# bg_MCU.net
KiCad netlist of a schematic drawn in Altium Designer
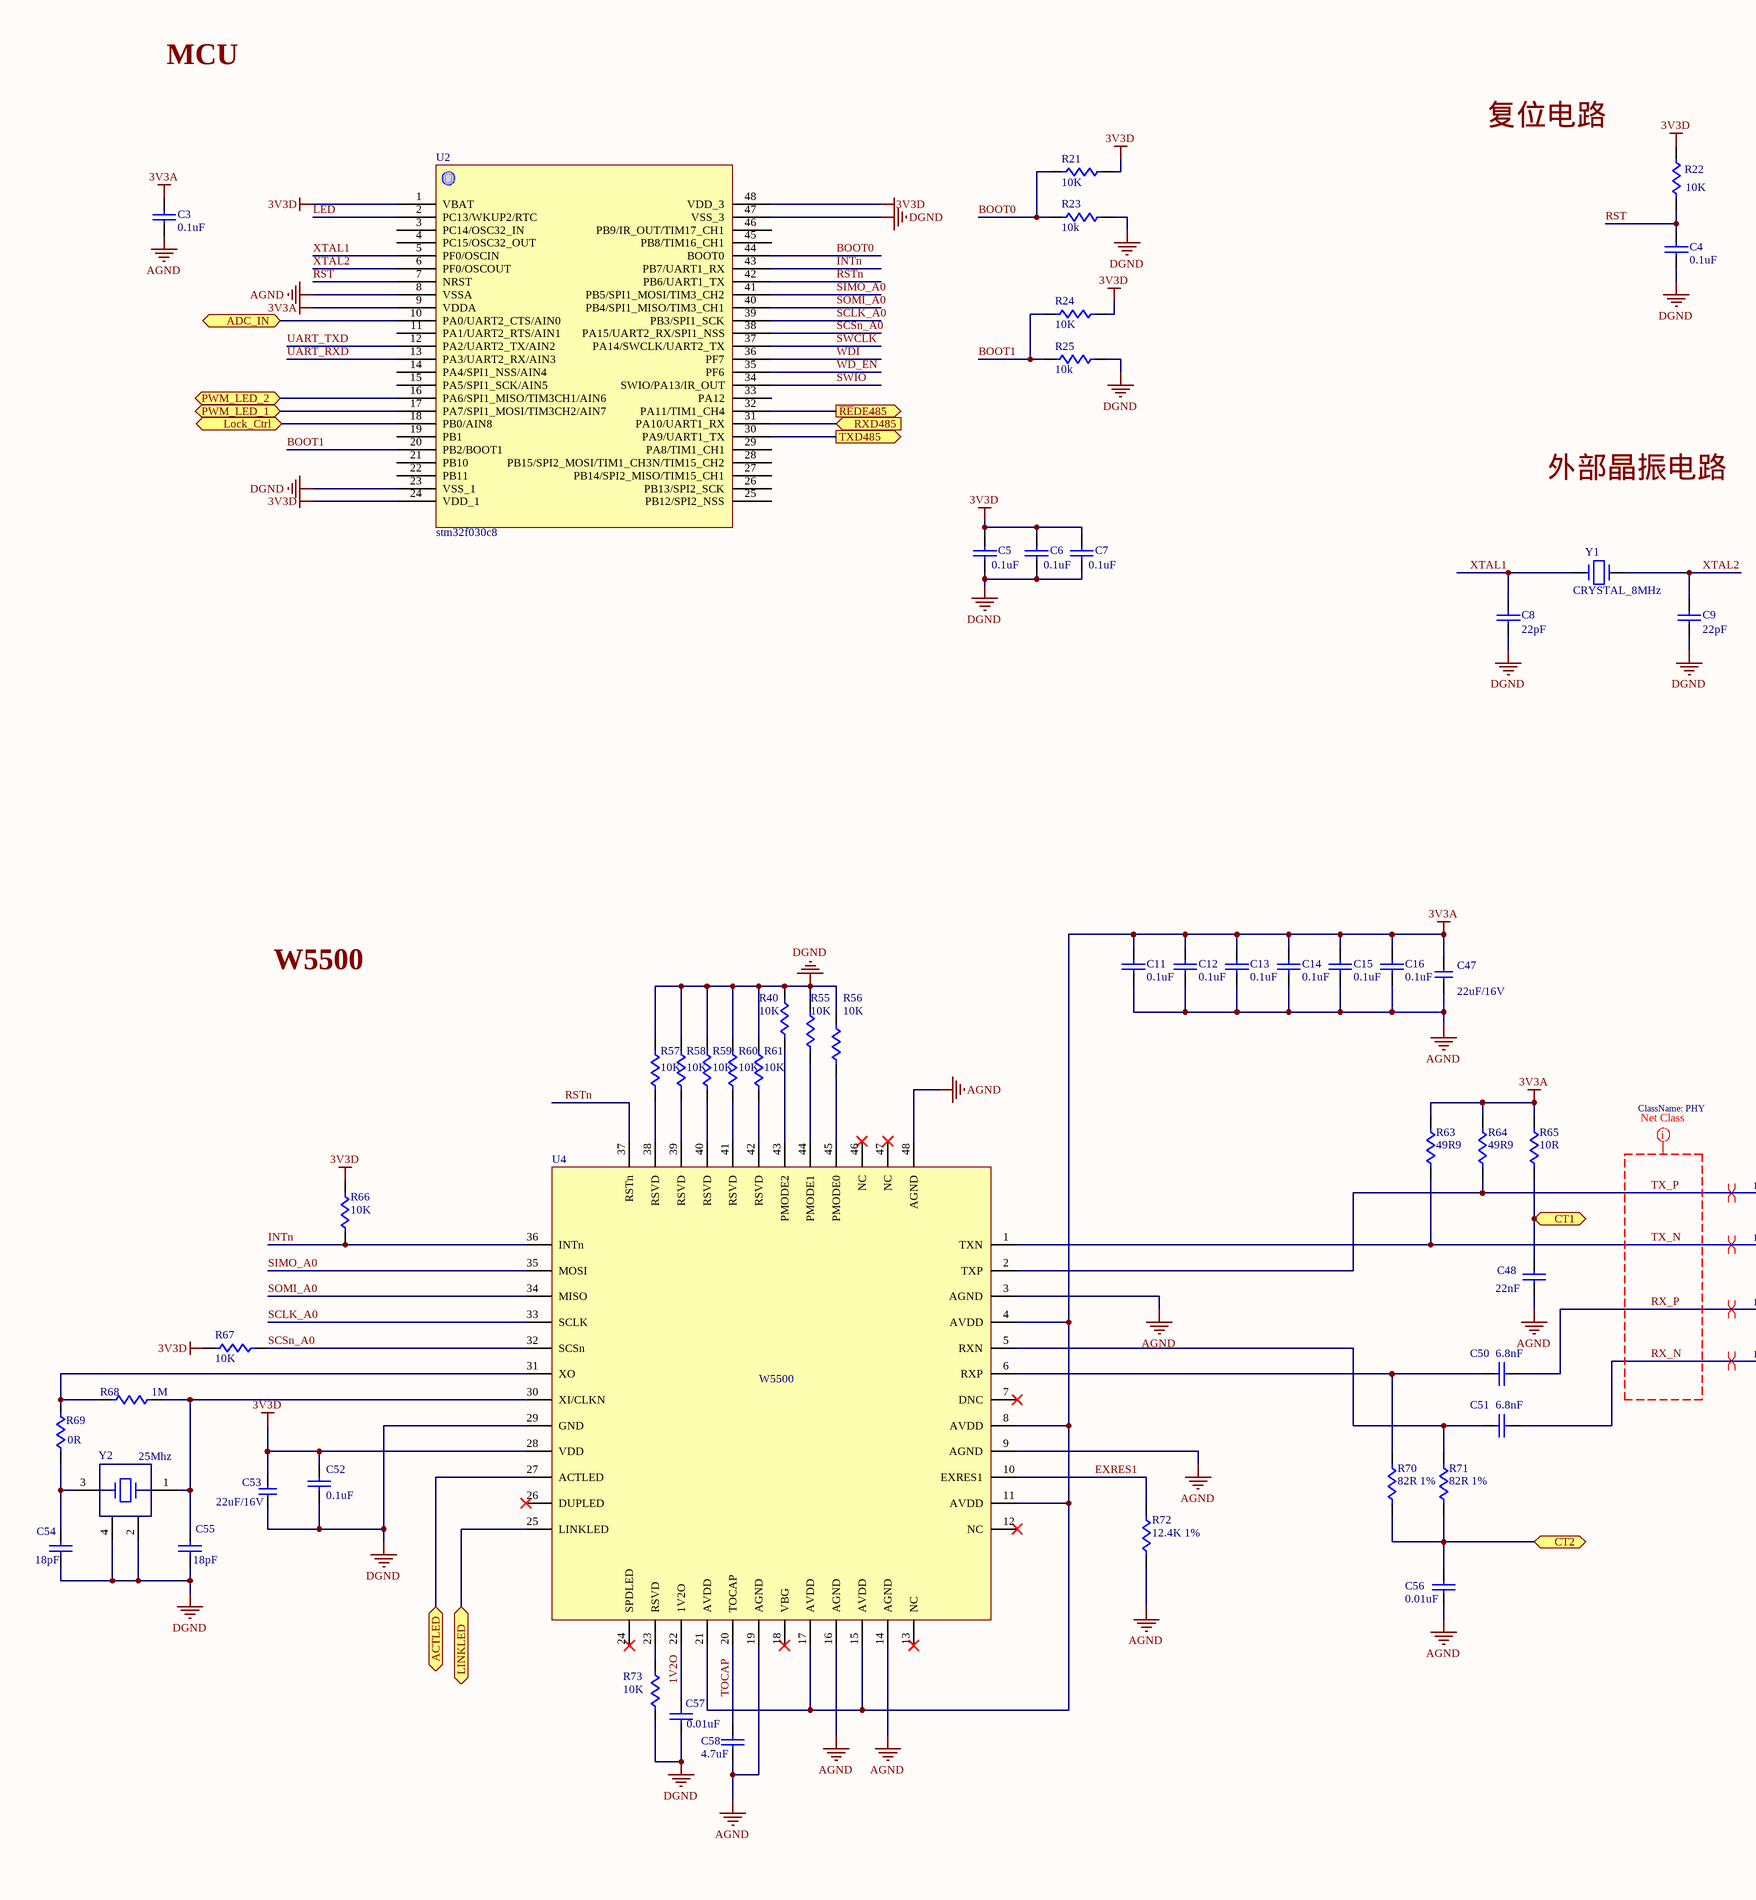
[diagram p0: bg_MCU.SchDoc, left]
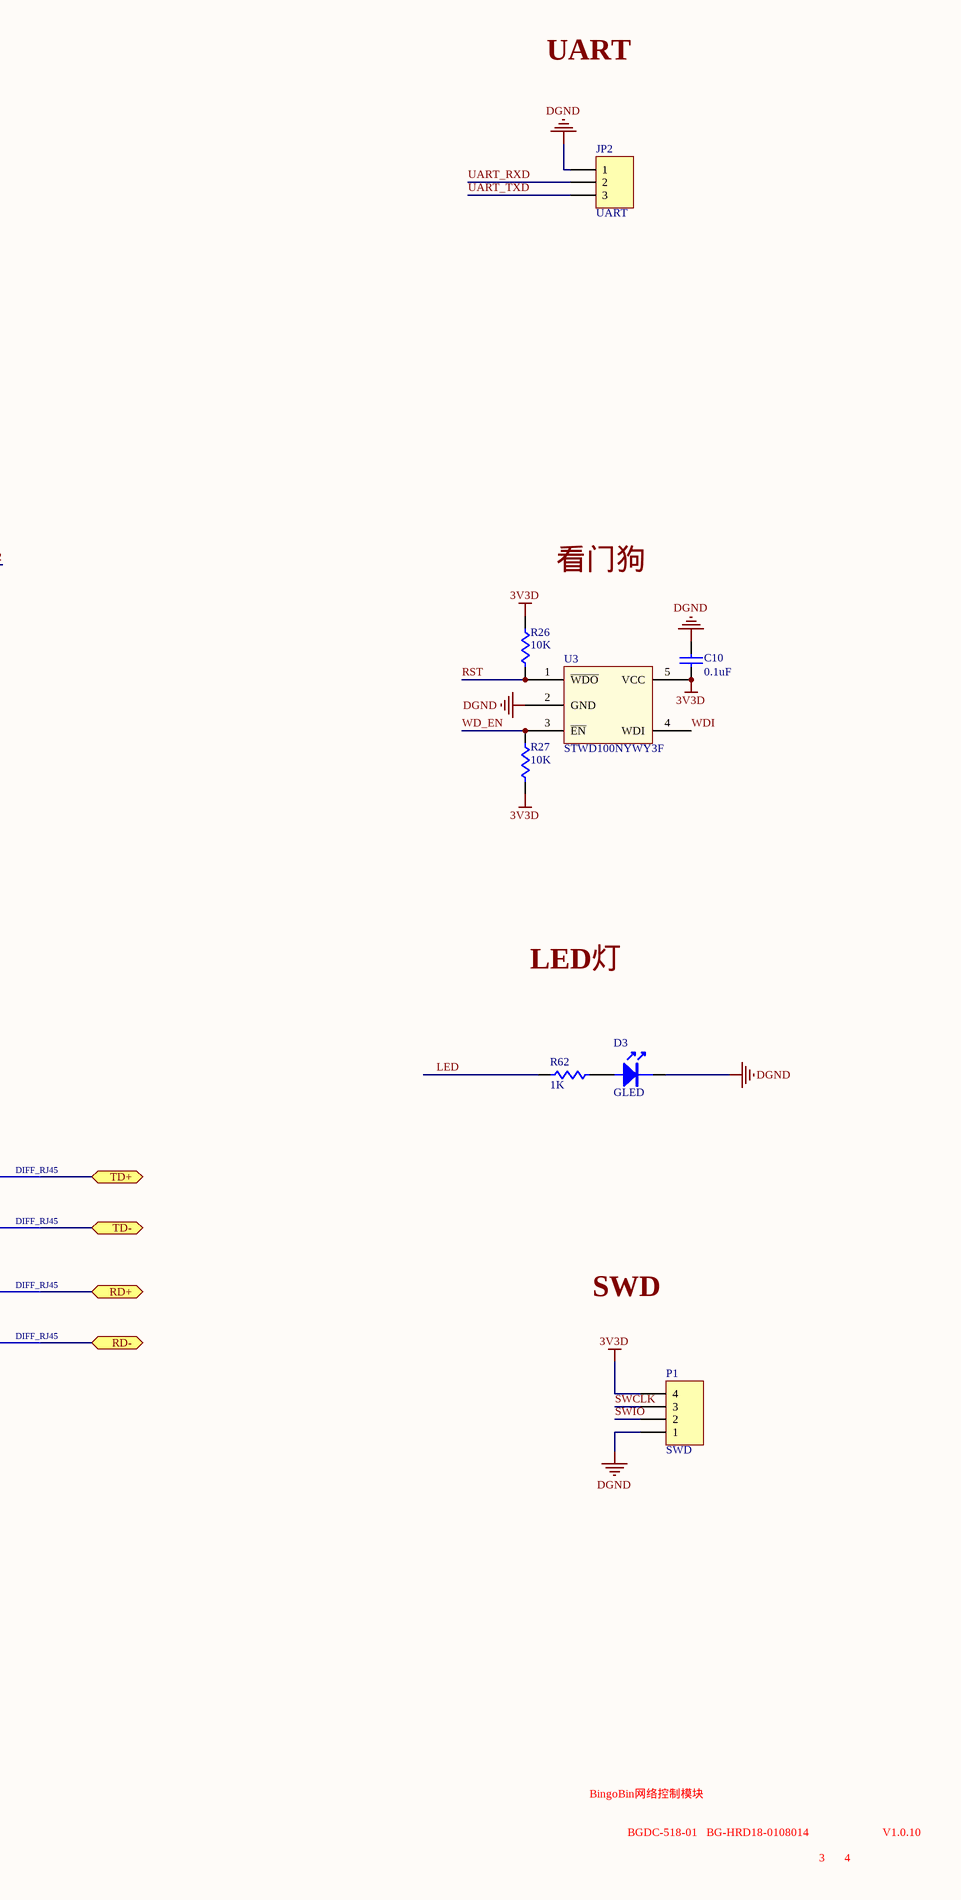
[diagram p1: bg_MCU.SchDoc, right]

(export (version "E")
  (design (tool "Eeschema 10.0.6"))
  (components
    (comp (ref "C3")
      (value "0.1uF")
      (footprint "C0603")
      (description "Capacitor, Ceramic, 0.1uF, 16V, 10%, 0603, X7R")
      (libsource (lib "bg_sch") (part "C0603"))
    )
    (comp (ref "C4")
      (value "0.1uF")
      (footprint "C0603")
      (description "Capacitor, Ceramic, 0.1uF, 16V, 10%, 0603, X7R")
      (libsource (lib "bg_sch") (part "C0603"))
    )
    (comp (ref "C5")
      (value "0.1uF")
      (footprint "C0603")
      (description "Capacitor, Ceramic, 0.1uF, 16V, 10%, 0603, X7R")
      (libsource (lib "bg_sch") (part "C0603"))
    )
    (comp (ref "C6")
      (value "0.1uF")
      (footprint "C0603")
      (description "Capacitor, Ceramic, 0.1uF, 16V, 10%, 0603, X7R")
      (libsource (lib "bg_sch") (part "C0603"))
    )
    (comp (ref "C7")
      (value "0.1uF")
      (footprint "C0603")
      (description "Capacitor, Ceramic, 0.1uF, 16V, 10%, 0603, X7R")
      (libsource (lib "bg_sch") (part "C0603"))
    )
    (comp (ref "C8")
      (value "22pF")
      (footprint "C0603")
      (description "Capacitor, Ceramic, 22pF, 50V, 5%, 0603, COG")
      (libsource (lib "bg_sch") (part "C0603"))
    )
    (comp (ref "C9")
      (value "22pF")
      (footprint "C0603")
      (description "Capacitor, Ceramic, 22pF, 50V, 5%, 0603, COG")
      (libsource (lib "bg_sch") (part "C0603"))
    )
    (comp (ref "C10")
      (value "0.1uF")
      (footprint "C0603")
      (description "Capacitor, Ceramic, 0.1uF, 16V, 10%, 0603, X7R")
      (libsource (lib "bg_sch") (part "C0603"))
    )
    (comp (ref "C11")
      (value "0.1uF")
      (footprint "C0603")
      (description "Capacitor, Ceramic, 0.1uF, 16V, 10%, 0603, X7R")
      (libsource (lib "bg_sch") (part "C0603"))
    )
    (comp (ref "C12")
      (value "0.1uF")
      (footprint "C0603")
      (description "Capacitor, Ceramic, 0.1uF, 16V, 10%, 0603, X7R")
      (libsource (lib "bg_sch") (part "C0603"))
    )
    (comp (ref "C13")
      (value "0.1uF")
      (footprint "C0603")
      (description "Capacitor, Ceramic, 0.1uF, 16V, 10%, 0603, X7R")
      (libsource (lib "bg_sch") (part "C0603"))
    )
    (comp (ref "C14")
      (value "0.1uF")
      (footprint "C0603")
      (description "Capacitor, Ceramic, 0.1uF, 16V, 10%, 0603, X7R")
      (libsource (lib "bg_sch") (part "C0603"))
    )
    (comp (ref "C15")
      (value "0.1uF")
      (footprint "C0603")
      (description "Capacitor, Ceramic, 0.1uF, 16V, 10%, 0603, X7R")
      (libsource (lib "bg_sch") (part "C0603"))
    )
    (comp (ref "C16")
      (value "0.1uF")
      (footprint "C0603")
      (description "Capacitor, Ceramic, 0.1uF, 16V, 10%, 0603, X7R")
      (libsource (lib "bg_sch") (part "C0603"))
    )
    (comp (ref "C47")
      (value "22uF/16V")
      (footprint "C1210")
      (description "Capacitor, Ceramic, 10uF,16V, 10%,1210,X5R")
      (fields (field (name "PART NUMBER") "C0603-4µ7") (field (name "PUBLISHER") "Nordic Semiconductor"))
      (libsource (lib "sistalk") (part "CAP_0603"))
    )
    (comp (ref "C48")
      (value "22nF")
      (footprint "C0603")
      (description "Capacitor, Ceramic, 22nF, 25V, 10%, 0603, X7R")
      (libsource (lib "bg_sch") (part "C0603"))
    )
    (comp (ref "C50")
      (value "6.8nF")
      (footprint "C0603")
      (description "Capacitor, Ceramic, 6.8nF, 50V, 10%, 0603, X7R")
      (libsource (lib "bg_sch") (part "C0603"))
    )
    (comp (ref "C51")
      (value "6.8nF")
      (footprint "C0603")
      (description "Capacitor, Ceramic, 6.8nF, 50V, 10%, 0603, X7R")
      (libsource (lib "bg_sch") (part "C0603"))
    )
    (comp (ref "C52")
      (value "0.1uF")
      (footprint "C0603")
      (description "Capacitor, Ceramic, 0.1uF, 16V, 10%, 0603, X7R")
      (libsource (lib "bg_sch") (part "C0603"))
    )
    (comp (ref "C53")
      (value "22uF/16V")
      (footprint "C1210")
      (description "Capacitor, Ceramic, 10uF,16V, 10%,1210,X5R")
      (fields (field (name "PART NUMBER") "C0603-4µ7") (field (name "PUBLISHER") "Nordic Semiconductor"))
      (libsource (lib "sistalk") (part "CAP_0603"))
    )
    (comp (ref "C54")
      (value "18pF")
      (footprint "C0603")
      (description "Capacitor, Ceramic, 18pF, 50V, 5%, 0603, COG")
      (libsource (lib "bg_sch") (part "C0603"))
    )
    (comp (ref "C55")
      (value "18pF")
      (footprint "C0603")
      (description "Capacitor, Ceramic, 18pF, 50V, 5%, 0603, COG")
      (libsource (lib "bg_sch") (part "C0603"))
    )
    (comp (ref "C56")
      (value "0.01uF")
      (footprint "C0603")
      (description "Capacitor, Ceramic, 0.01uF, 50V, 10%, 0603, X7R")
      (libsource (lib "bg_sch") (part "C0603"))
    )
    (comp (ref "C57")
      (value "0.01uF")
      (footprint "C0603")
      (description "Capacitor, Ceramic, 0.01uF, 50V, 10%, 0603, X7R")
      (libsource (lib "bg_sch") (part "C0603"))
    )
    (comp (ref "C58")
      (value "4.7uF")
      (footprint "C0603")
      (description "Capacitor, Ceramic, 4.7uF, 16V, 10%, 0603, X7R")
      (libsource (lib "bg_sch") (part "C0603"))
    )
    (comp (ref "D3")
      (value "GLED")
      (footprint "LED-0805")
      (description "翠绿色 贴片LED ( Iv=220-270mcd @IF=5mA) ")
      (libsource (lib "bg_sch") (part "LED_0805"))
    )
    (comp (ref "JP2")
      (value "UART")
      (footprint "HDR1X3")
      (description "Header, 3-Pin, Single row")
      (fields (field (name "PUBLISHER") "Altium Limited"))
      (libsource (lib "Miscellaneous Connectors") (part "Header 3"))
    )
    (comp (ref "P1")
      (value "SWD")
      (footprint "HDR1X4")
      (description "Header, 4-Pin")
      (fields (field (name "PUBLISHER") "Altium Limited"))
      (libsource (lib "Miscellaneous Connectors") (part "Header 4"))
    )
    (comp (ref "R21")
      (value "10K")
      (footprint "R0603")
      (description "RES, THICK FILM, 4.7K, 5%, 1/10W, 0603")
      (libsource (lib "bg_sch") (part "R0603"))
    )
    (comp (ref "R22")
      (value "10K")
      (footprint "R0603")
      (description "RES, THICK FILM, 4.7K, 5%, 1/10W, 0603")
      (libsource (lib "bg_sch") (part "R0603"))
    )
    (comp (ref "R23")
      (value "10k")
      (footprint "R0603")
      (description "RES, THICK FILM, 4.7K, 5%, 1/10W, 0603")
      (libsource (lib "bg_sch") (part "R0603"))
    )
    (comp (ref "R24")
      (value "10K")
      (footprint "R0603")
      (description "RES, THICK FILM, 4.7K, 5%, 1/10W, 0603")
      (libsource (lib "bg_sch") (part "R0603"))
    )
    (comp (ref "R25")
      (value "10k")
      (footprint "R0603")
      (description "RES, THICK FILM, 4.7K, 5%, 1/10W, 0603")
      (libsource (lib "bg_sch") (part "R0603"))
    )
    (comp (ref "R26")
      (value "10K")
      (footprint "R0603")
      (description "RES, THICK FILM, 10K, 5%, 1/10W, 0603")
      (libsource (lib "bg_sch") (part "R0603"))
    )
    (comp (ref "R27")
      (value "10K")
      (footprint "R0603")
      (description "RES, THICK FILM, 10K, 5%, 1/10W, 0603")
      (libsource (lib "bg_sch") (part "R0603"))
    )
    (comp (ref "R40")
      (value "10K")
      (footprint "R0603")
      (description "RES, THICK FILM, 10K, 5%, 1/10W, 0603")
      (libsource (lib "bg_sch") (part "R0603"))
    )
    (comp (ref "R55")
      (value "10K")
      (footprint "R0603")
      (description "RES, THICK FILM, 10K, 5%, 1/10W, 0603")
      (libsource (lib "bg_sch") (part "R0603"))
    )
    (comp (ref "R56")
      (value "10K")
      (footprint "R0603")
      (description "RES, THICK FILM, 10K, 5%, 1/10W, 0603")
      (libsource (lib "bg_sch") (part "R0603"))
    )
    (comp (ref "R57")
      (value "10K")
      (footprint "R0603")
      (description "RES, THICK FILM, 10K, 5%, 1/10W, 0603")
      (libsource (lib "bg_sch") (part "R0603"))
    )
    (comp (ref "R58")
      (value "10K")
      (footprint "R0603")
      (description "RES, THICK FILM, 10K, 5%, 1/10W, 0603")
      (libsource (lib "bg_sch") (part "R0603"))
    )
    (comp (ref "R59")
      (value "10K")
      (footprint "R0603")
      (description "RES, THICK FILM, 10K, 5%, 1/10W, 0603")
      (libsource (lib "bg_sch") (part "R0603"))
    )
    (comp (ref "R60")
      (value "10K")
      (footprint "R0603")
      (description "RES, THICK FILM, 10K, 5%, 1/10W, 0603")
      (libsource (lib "bg_sch") (part "R0603"))
    )
    (comp (ref "R61")
      (value "10K")
      (footprint "R0603")
      (description "RES, THICK FILM, 10K, 5%, 1/10W, 0603")
      (libsource (lib "bg_sch") (part "R0603"))
    )
    (comp (ref "R62")
      (value "1K")
      (footprint "R0603")
      (description "RES, THICK FILM, 1K, 5%, 1/10W, 0603")
      (libsource (lib "bg_sch") (part "R0603"))
    )
    (comp (ref "R63")
      (value "49R9")
      (footprint "R0603")
      (description "RES, THICK FILM, 49.9 OHM, 1%, 1/10W, 0603")
      (libsource (lib "bg_sch") (part "R0603"))
    )
    (comp (ref "R64")
      (value "49R9")
      (footprint "R0603")
      (description "RES, THICK FILM, 49.9 OHM, 1%, 1/10W, 0603")
      (libsource (lib "bg_sch") (part "R0603"))
    )
    (comp (ref "R65")
      (value "10R")
      (footprint "R0603")
      (description "RES, THICK FILM, 10 OHM, 5%, 1/10W, 0603")
      (libsource (lib "bg_sch") (part "R0603"))
    )
    (comp (ref "R66")
      (value "10K")
      (footprint "R0603")
      (description "RES, THICK FILM, 10K, 5%, 1/10W, 0603")
      (libsource (lib "bg_sch") (part "R0603"))
    )
    (comp (ref "R67")
      (value "10K")
      (footprint "R0603")
      (description "RES, THICK FILM, 10K, 5%, 1/10W, 0603")
      (libsource (lib "bg_sch") (part "R0603"))
    )
    (comp (ref "R68")
      (value "1M")
      (footprint "R0603")
      (description "RES, THICK FILM, 1M, 5%, 1/10W, 0603")
      (libsource (lib "bg_sch") (part "R0603"))
    )
    (comp (ref "R69")
      (value "0R")
      (footprint "R0603")
      (description "RES, THICK FILM, 0 OHM, 1%, 1/10W, 0603")
      (libsource (lib "bg_sch") (part "R0603"))
    )
    (comp (ref "R70")
      (value "82R 1%")
      (footprint "R0603")
      (description "RES, THICK FILM, 82 OHM, 5%, 1/10W, 0603")
      (libsource (lib "bg_sch") (part "R0603"))
    )
    (comp (ref "R71")
      (value "82R 1%")
      (footprint "R0603")
      (description "RES, THICK FILM, 82 OHM, 5%, 1/10W, 0603")
      (libsource (lib "bg_sch") (part "R0603"))
    )
    (comp (ref "R72")
      (value "12.4K 1%")
      (footprint "R0603")
      (description "RES, THICK FILM, 12.4K, 1%, 1/10W, 0603")
      (libsource (lib "bg_sch") (part "R0603"))
    )
    (comp (ref "R73")
      (value "10K")
      (footprint "R0603")
      (description "RES, THICK FILM, 10K, 5%, 1/10W, 0603")
      (libsource (lib "bg_sch") (part "R0603"))
    )
    (comp (ref "U2")
      (value "stm32f030c8")
      (footprint "LQFP48")
      (description "mcu  LQFP-48_7x7x05P")
      (libsource (lib "bingo") (part "stm32f030c8"))
    )
    (comp (ref "U3")
      (value "STWD100NYWY3F")
      (footprint "SOT23-5")
      (description "Watchdog timer circuit/1.6s")
      (libsource (lib "bingo") (part "STWD100"))
    )
    (comp (ref "U4")
      (value "W5500")
      (footprint "W5500-LQFP-48_7x7x05P")
      (description "TCP/IP嵌入式以太网控制器")
      (libsource (lib "bg_sch") (part "W5500"))
    )
    (comp (ref "Y1")
      (value "CRYSTAL_8MHz")
      (footprint "8M_SMD_CRYSTAL")
      (description "20PF 20PPM -40~+85℃ 编带")
      (libsource (lib "bg_sch") (part "CRYSTAL_32.768k"))
    )
    (comp (ref "Y2")
      (value "25Mhz")
      (footprint "25MHz-SMD-3225_4P")
      (description "XTAL S3225 25M 12pF 10ppm 40R -20~70℃ ")
      (libsource (lib "bg_sch") (part "25Mhz"))
    )
  )
  (nets
    (net (code "1") (name "/1V2O") (class "Default")
      (node (ref "C57") (pin "1") (pinfunction "1_1") (pintype "passive"))
      (node (ref "U4") (pin "22") (pinfunction "1V2O_22") (pintype "passive"))
    )
    (net (code "2") (name "/ACTLED") (class "Default")
      (node (ref "U4") (pin "27") (pinfunction "ACTLED_27") (pintype "passive"))
    )
    (net (code "3") (name "/ADC_IN") (class "Default")
      (node (ref "U2") (pin "10") (pinfunction "PA0/UART2_CTS/AIN0_10") (pintype "passive"))
    )
    (net (code "4") (name "/BOOT0") (class "Default")
      (node (ref "R21") (pin "2") (pinfunction "2_2") (pintype "passive"))
      (node (ref "R23") (pin "2") (pinfunction "2_2") (pintype "passive"))
      (node (ref "U2") (pin "44") (pinfunction "BOOT0_44") (pintype "passive"))
    )
    (net (code "5") (name "/BOOT1") (class "Default")
      (node (ref "R24") (pin "2") (pinfunction "2_2") (pintype "passive"))
      (node (ref "R25") (pin "2") (pinfunction "2_2") (pintype "passive"))
      (node (ref "U2") (pin "20") (pinfunction "PB2/BOOT1_20") (pintype "passive"))
    )
    (net (code "6") (name "/CT1") (class "Default")
      (node (ref "C48") (pin "1") (pinfunction "1_1") (pintype "passive"))
      (node (ref "R65") (pin "1") (pinfunction "1_1") (pintype "passive"))
    )
    (net (code "7") (name "/CT2") (class "Default")
      (node (ref "C56") (pin "1") (pinfunction "1_1") (pintype "passive"))
      (node (ref "R70") (pin "1") (pinfunction "1_1") (pintype "passive"))
      (node (ref "R71") (pin "1") (pinfunction "1_1") (pintype "passive"))
    )
    (net (code "8") (name "/EXRES1") (class "Default")
      (node (ref "R72") (pin "2") (pinfunction "2_2") (pintype "passive"))
      (node (ref "U4") (pin "10") (pinfunction "EXRES1_10") (pintype "passive"))
    )
    (net (code "9") (name "/INTn") (class "Default")
      (node (ref "R66") (pin "1") (pinfunction "1_1") (pintype "passive"))
      (node (ref "U2") (pin "43") (pinfunction "PB7/UART1_RX_43") (pintype "passive"))
      (node (ref "U4") (pin "36") (pinfunction "INTn_36") (pintype "passive"))
    )
    (net (code "10") (name "/LED") (class "Default")
      (node (ref "R62") (pin "2") (pinfunction "2_2") (pintype "passive"))
      (node (ref "U2") (pin "2") (pinfunction "PC13/WKUP2/RTC_2") (pintype "passive"))
    )
    (net (code "11") (name "/LINKLED") (class "Default")
      (node (ref "U4") (pin "25") (pinfunction "LINKLED_25") (pintype "passive"))
    )
    (net (code "12") (name "/Lock_Ctrl") (class "Default")
      (node (ref "U2") (pin "18") (pinfunction "PB0/AIN8_18") (pintype "passive"))
    )
    (net (code "13") (name "/PWM_LED_1") (class "Default")
      (node (ref "U2") (pin "17") (pinfunction "PA7/SPI1_MOSI/TIM3CH2/AIN7_17") (pintype "passive"))
    )
    (net (code "14") (name "/PWM_LED_2") (class "Default")
      (node (ref "U2") (pin "16") (pinfunction "PA6/SPI1_MISO/TIM3CH1/AIN6_16") (pintype "passive"))
    )
    (net (code "15") (name "/RST") (class "Default")
      (node (ref "C4") (pin "2") (pinfunction "2_2") (pintype "passive"))
      (node (ref "R22") (pin "1") (pinfunction "1_1") (pintype "passive"))
      (node (ref "R26") (pin "1") (pinfunction "1_1") (pintype "passive"))
      (node (ref "U2") (pin "7") (pinfunction "NRST_7") (pintype "passive"))
      (node (ref "U3") (pin "1") (pinfunction "~{WDO}_1") (pintype "passive"))
    )
    (net (code "16") (name "/RSTn") (class "Default")
      (node (ref "U2") (pin "42") (pinfunction "PB6/UART1_TX_42") (pintype "passive"))
      (node (ref "U4") (pin "37") (pinfunction "RSTn_37") (pintype "passive"))
    )
    (net (code "17") (name "/RXD485") (class "Default")
      (node (ref "U2") (pin "31") (pinfunction "PA10/UART1_RX_31") (pintype "passive"))
    )
    (net (code "18") (name "/RX_N") (class "Default")
      (node (ref "C51") (pin "2") (pinfunction "2_2") (pintype "passive"))
    )
    (net (code "19") (name "/RX_P") (class "Default")
      (node (ref "C50") (pin "2") (pinfunction "2_2") (pintype "passive"))
    )
    (net (code "20") (name "/SCLK_A0") (class "Default")
      (node (ref "U2") (pin "39") (pinfunction "PB3/SPI1_SCK_39") (pintype "passive"))
      (node (ref "U4") (pin "33") (pinfunction "SCLK_33") (pintype "passive"))
    )
    (net (code "21") (name "/SCSn_A0") (class "Default")
      (node (ref "R67") (pin "1") (pinfunction "1_1") (pintype "passive"))
      (node (ref "U2") (pin "38") (pinfunction "PA15/UART2_RX/SPI1_NSS_38") (pintype "passive"))
      (node (ref "U4") (pin "32") (pinfunction "SCSn_32") (pintype "passive"))
    )
    (net (code "22") (name "/SIMO_A0") (class "Default")
      (node (ref "U2") (pin "41") (pinfunction "PB5/SPI1_MOSI/TIM3_CH2_41") (pintype "passive"))
      (node (ref "U4") (pin "35") (pinfunction "MOSI_35") (pintype "passive"))
    )
    (net (code "23") (name "/SOMI_A0") (class "Default")
      (node (ref "U2") (pin "40") (pinfunction "PB4/SPI1_MISO/TIM3_CH1_40") (pintype "passive"))
      (node (ref "U4") (pin "34") (pinfunction "MISO_34") (pintype "passive"))
    )
    (net (code "24") (name "/SWCLK") (class "Default")
      (node (ref "P1") (pin "3") (pinfunction "3_3") (pintype "passive"))
      (node (ref "U2") (pin "37") (pinfunction "PA14/SWCLK/UART2_TX_37") (pintype "passive"))
    )
    (net (code "25") (name "/SWIO") (class "Default")
      (node (ref "P1") (pin "2") (pinfunction "2_2") (pintype "passive"))
      (node (ref "U2") (pin "34") (pinfunction "SWIO/PA13/IR_OUT_34") (pintype "passive"))
    )
    (net (code "26") (name "/TOCAP") (class "Default")
      (node (ref "C58") (pin "1") (pinfunction "1_1") (pintype "passive"))
      (node (ref "U4") (pin "20") (pinfunction "TOCAP_20") (pintype "passive"))
    )
    (net (code "27") (name "/TXD485") (class "Default")
      (node (ref "U2") (pin "30") (pinfunction "PA9/UART1_TX_30") (pintype "passive"))
    )
    (net (code "28") (name "/TX_N") (class "Default")
      (node (ref "R63") (pin "1") (pinfunction "1_1") (pintype "passive"))
      (node (ref "U4") (pin "1") (pinfunction "TXN_1") (pintype "passive"))
    )
    (net (code "29") (name "/TX_P") (class "Default")
      (node (ref "R64") (pin "1") (pinfunction "1_1") (pintype "passive"))
      (node (ref "U4") (pin "2") (pinfunction "TXP_2") (pintype "passive"))
    )
    (net (code "30") (name "/UART_RXD") (class "Default")
      (node (ref "JP2") (pin "2") (pinfunction "2_2") (pintype "passive"))
      (node (ref "U2") (pin "13") (pinfunction "PA3/UART2_RX/AIN3_13") (pintype "passive"))
    )
    (net (code "31") (name "/UART_TXD") (class "Default")
      (node (ref "JP2") (pin "3") (pinfunction "3_3") (pintype "passive"))
      (node (ref "U2") (pin "12") (pinfunction "PA2/UART2_TX/AIN2_12") (pintype "passive"))
    )
    (net (code "32") (name "/WDI") (class "Default")
      (node (ref "U2") (pin "36") (pinfunction "PF7_36") (pintype "passive"))
      (node (ref "U3") (pin "4") (pinfunction "WDI_4") (pintype "passive"))
    )
    (net (code "33") (name "/WD_EN") (class "Default")
      (node (ref "R27") (pin "2") (pinfunction "2_2") (pintype "passive"))
      (node (ref "U2") (pin "35") (pinfunction "PF6_35") (pintype "passive"))
      (node (ref "U3") (pin "3") (pinfunction "~{EN}_3") (pintype "passive"))
    )
    (net (code "34") (name "/XTAL1") (class "Default")
      (node (ref "C8") (pin "1") (pinfunction "1_1") (pintype "passive"))
      (node (ref "U2") (pin "5") (pinfunction "PF0/OSCIN_5") (pintype "passive"))
      (node (ref "Y1") (pin "1") (pinfunction "1_1") (pintype "passive"))
    )
    (net (code "35") (name "/XTAL2") (class "Default")
      (node (ref "C9") (pin "1") (pinfunction "1_1") (pintype "passive"))
      (node (ref "U2") (pin "6") (pinfunction "PF0/OSCOUT_6") (pintype "passive"))
      (node (ref "Y1") (pin "2") (pinfunction "2_2") (pintype "passive"))
    )
    (net (code "36") (name "/~{RE}DE485") (class "Default")
      (node (ref "U2") (pin "32") (pinfunction "PA11/TIM1_CH4_32") (pintype "passive"))
    )
    (net (code "37") (name "3V3A") (class "Default")
      (node (ref "C11") (pin "1") (pinfunction "1_1") (pintype "passive"))
      (node (ref "C12") (pin "1") (pinfunction "1_1") (pintype "passive"))
      (node (ref "C13") (pin "1") (pinfunction "1_1") (pintype "passive"))
      (node (ref "C14") (pin "1") (pinfunction "1_1") (pintype "passive"))
      (node (ref "C15") (pin "1") (pinfunction "1_1") (pintype "passive"))
      (node (ref "C16") (pin "1") (pinfunction "1_1") (pintype "passive"))
      (node (ref "C3") (pin "1") (pinfunction "1_1") (pintype "passive"))
      (node (ref "C47") (pin "2") (pinfunction "2_2") (pintype "passive"))
      (node (ref "R63") (pin "2") (pinfunction "2_2") (pintype "passive"))
      (node (ref "R64") (pin "2") (pinfunction "2_2") (pintype "passive"))
      (node (ref "R65") (pin "2") (pinfunction "2_2") (pintype "passive"))
      (node (ref "U2") (pin "9") (pinfunction "VDDA_9") (pintype "passive"))
      (node (ref "U4") (pin "11") (pinfunction "AVDD_11") (pintype "passive"))
      (node (ref "U4") (pin "15") (pinfunction "AVDD_15") (pintype "passive"))
      (node (ref "U4") (pin "17") (pinfunction "AVDD_17") (pintype "passive"))
      (node (ref "U4") (pin "21") (pinfunction "AVDD_21") (pintype "passive"))
      (node (ref "U4") (pin "4") (pinfunction "AVDD_4") (pintype "passive"))
      (node (ref "U4") (pin "8") (pinfunction "AVDD_8") (pintype "passive"))
    )
    (net (code "38") (name "3V3D") (class "Default")
      (node (ref "C10") (pin "2") (pinfunction "2_2") (pintype "passive"))
      (node (ref "C5") (pin "2") (pinfunction "2_2") (pintype "passive"))
      (node (ref "C52") (pin "1") (pinfunction "1_1") (pintype "passive"))
      (node (ref "C53") (pin "2") (pinfunction "2_2") (pintype "passive"))
      (node (ref "C6") (pin "2") (pinfunction "2_2") (pintype "passive"))
      (node (ref "C7") (pin "2") (pinfunction "2_2") (pintype "passive"))
      (node (ref "P1") (pin "4") (pinfunction "4_4") (pintype "passive"))
      (node (ref "R21") (pin "1") (pinfunction "1_1") (pintype "passive"))
      (node (ref "R22") (pin "2") (pinfunction "2_2") (pintype "passive"))
      (node (ref "R24") (pin "1") (pinfunction "1_1") (pintype "passive"))
      (node (ref "R26") (pin "2") (pinfunction "2_2") (pintype "passive"))
      (node (ref "R27") (pin "1") (pinfunction "1_1") (pintype "passive"))
      (node (ref "R66") (pin "2") (pinfunction "2_2") (pintype "passive"))
      (node (ref "R67") (pin "2") (pinfunction "2_2") (pintype "passive"))
      (node (ref "U2") (pin "1") (pinfunction "VBAT_1") (pintype "passive"))
      (node (ref "U2") (pin "24") (pinfunction "VDD_1_24") (pintype "passive"))
      (node (ref "U2") (pin "48") (pinfunction "VDD_3_48") (pintype "passive"))
      (node (ref "U3") (pin "5") (pinfunction "VCC_5") (pintype "passive"))
      (node (ref "U4") (pin "28") (pinfunction "VDD_28") (pintype "passive"))
    )
    (net (code "39") (name "AGND") (class "Default")
      (node (ref "C11") (pin "2") (pinfunction "2_2") (pintype "passive"))
      (node (ref "C12") (pin "2") (pinfunction "2_2") (pintype "passive"))
      (node (ref "C13") (pin "2") (pinfunction "2_2") (pintype "passive"))
      (node (ref "C14") (pin "2") (pinfunction "2_2") (pintype "passive"))
      (node (ref "C15") (pin "2") (pinfunction "2_2") (pintype "passive"))
      (node (ref "C16") (pin "2") (pinfunction "2_2") (pintype "passive"))
      (node (ref "C3") (pin "2") (pinfunction "2_2") (pintype "passive"))
      (node (ref "C47") (pin "1") (pinfunction "1_1") (pintype "passive"))
      (node (ref "C48") (pin "2") (pinfunction "2_2") (pintype "passive"))
      (node (ref "C56") (pin "2") (pinfunction "2_2") (pintype "passive"))
      (node (ref "C58") (pin "2") (pinfunction "2_2") (pintype "passive"))
      (node (ref "R72") (pin "1") (pinfunction "1_1") (pintype "passive"))
      (node (ref "U2") (pin "8") (pinfunction "VSSA_8") (pintype "passive"))
      (node (ref "U4") (pin "14") (pinfunction "AGND_14") (pintype "passive"))
      (node (ref "U4") (pin "16") (pinfunction "AGND_16") (pintype "passive"))
      (node (ref "U4") (pin "19") (pinfunction "AGND_19") (pintype "passive"))
      (node (ref "U4") (pin "3") (pinfunction "AGND_3") (pintype "passive"))
      (node (ref "U4") (pin "48") (pinfunction "AGND_48") (pintype "passive"))
      (node (ref "U4") (pin "9") (pinfunction "AGND_9") (pintype "passive"))
    )
    (net (code "40") (name "DGND") (class "Default")
      (node (ref "C10") (pin "1") (pinfunction "1_1") (pintype "passive"))
      (node (ref "C4") (pin "1") (pinfunction "1_1") (pintype "passive"))
      (node (ref "C5") (pin "1") (pinfunction "1_1") (pintype "passive"))
      (node (ref "C52") (pin "2") (pinfunction "2_2") (pintype "passive"))
      (node (ref "C53") (pin "1") (pinfunction "1_1") (pintype "passive"))
      (node (ref "C54") (pin "2") (pinfunction "2_2") (pintype "passive"))
      (node (ref "C55") (pin "2") (pinfunction "2_2") (pintype "passive"))
      (node (ref "C57") (pin "2") (pinfunction "2_2") (pintype "passive"))
      (node (ref "C6") (pin "1") (pinfunction "1_1") (pintype "passive"))
      (node (ref "C7") (pin "1") (pinfunction "1_1") (pintype "passive"))
      (node (ref "C8") (pin "2") (pinfunction "2_2") (pintype "passive"))
      (node (ref "C9") (pin "2") (pinfunction "2_2") (pintype "passive"))
      (node (ref "D3") (pin "2") (pinfunction "2_2") (pintype "passive"))
      (node (ref "JP2") (pin "1") (pinfunction "1_1") (pintype "passive"))
      (node (ref "P1") (pin "1") (pinfunction "1_1") (pintype "passive"))
      (node (ref "R23") (pin "1") (pinfunction "1_1") (pintype "passive"))
      (node (ref "R25") (pin "1") (pinfunction "1_1") (pintype "passive"))
      (node (ref "R40") (pin "2") (pinfunction "2_2") (pintype "passive"))
      (node (ref "R55") (pin "2") (pinfunction "2_2") (pintype "passive"))
      (node (ref "R56") (pin "2") (pinfunction "2_2") (pintype "passive"))
      (node (ref "R57") (pin "2") (pinfunction "2_2") (pintype "passive"))
      (node (ref "R58") (pin "2") (pinfunction "2_2") (pintype "passive"))
      (node (ref "R59") (pin "2") (pinfunction "2_2") (pintype "passive"))
      (node (ref "R60") (pin "2") (pinfunction "2_2") (pintype "passive"))
      (node (ref "R61") (pin "2") (pinfunction "2_2") (pintype "passive"))
      (node (ref "R73") (pin "1") (pinfunction "1_1") (pintype "passive"))
      (node (ref "U2") (pin "23") (pinfunction "VSS_1_23") (pintype "passive"))
      (node (ref "U2") (pin "47") (pinfunction "VSS_3_47") (pintype "passive"))
      (node (ref "U3") (pin "2") (pinfunction "GND_2") (pintype "passive"))
      (node (ref "U4") (pin "29") (pinfunction "GND_29") (pintype "passive"))
      (node (ref "Y2") (pin "2") (pinfunction "2_2") (pintype "passive"))
      (node (ref "Y2") (pin "4") (pinfunction "3_4") (pintype "passive"))
    )
    (net (code "41") (name "Net-(D3-Pad1)") (class "Default")
      (node (ref "D3") (pin "1") (pinfunction "1_1") (pintype "passive"))
      (node (ref "R62") (pin "1") (pinfunction "1_1") (pintype "passive"))
    )
    (net (code "42") (name "Net-(R57-Pad1)") (class "Default")
      (node (ref "R57") (pin "1") (pinfunction "1_1") (pintype "passive"))
      (node (ref "U4") (pin "38") (pinfunction "RSVD_38") (pintype "passive"))
    )
    (net (code "43") (name "Net-(R58-Pad1)") (class "Default")
      (node (ref "R58") (pin "1") (pinfunction "1_1") (pintype "passive"))
      (node (ref "U4") (pin "39") (pinfunction "RSVD_39") (pintype "passive"))
    )
    (net (code "44") (name "Net-(R59-Pad1)") (class "Default")
      (node (ref "R59") (pin "1") (pinfunction "1_1") (pintype "passive"))
      (node (ref "U4") (pin "40") (pinfunction "RSVD_40") (pintype "passive"))
    )
    (net (code "45") (name "Net-(R60-Pad1)") (class "Default")
      (node (ref "R60") (pin "1") (pinfunction "1_1") (pintype "passive"))
      (node (ref "U4") (pin "41") (pinfunction "RSVD_41") (pintype "passive"))
    )
    (net (code "46") (name "Net-(R61-Pad1)") (class "Default")
      (node (ref "R61") (pin "1") (pinfunction "1_1") (pintype "passive"))
      (node (ref "U4") (pin "42") (pinfunction "RSVD_42") (pintype "passive"))
    )
    (net (code "47") (name "Net-(R73-Pad2)") (class "Default")
      (node (ref "R73") (pin "2") (pinfunction "2_2") (pintype "passive"))
      (node (ref "U4") (pin "23") (pinfunction "RSVD_23") (pintype "passive"))
    )
    (net (code "48") (name "Net-(U4-PMODE0)") (class "Default")
      (node (ref "R56") (pin "1") (pinfunction "1_1") (pintype "passive"))
      (node (ref "U4") (pin "45") (pinfunction "PMODE0_45") (pintype "passive"))
    )
    (net (code "49") (name "Net-(U4-PMODE1)") (class "Default")
      (node (ref "R55") (pin "1") (pinfunction "1_1") (pintype "passive"))
      (node (ref "U4") (pin "44") (pinfunction "PMODE1_44") (pintype "passive"))
    )
    (net (code "50") (name "Net-(U4-PMODE2)") (class "Default")
      (node (ref "R40") (pin "1") (pinfunction "1_1") (pintype "passive"))
      (node (ref "U4") (pin "43") (pinfunction "PMODE2_43") (pintype "passive"))
    )
    (net (code "51") (name "Net-(U4-RXN)") (class "Default")
      (node (ref "C51") (pin "1") (pinfunction "1_1") (pintype "passive"))
      (node (ref "R71") (pin "2") (pinfunction "2_2") (pintype "passive"))
      (node (ref "U4") (pin "5") (pinfunction "RXN_5") (pintype "passive"))
    )
    (net (code "52") (name "Net-(U4-RXP)") (class "Default")
      (node (ref "C50") (pin "1") (pinfunction "1_1") (pintype "passive"))
      (node (ref "R70") (pin "2") (pinfunction "2_2") (pintype "passive"))
      (node (ref "U4") (pin "6") (pinfunction "RXP_6") (pintype "passive"))
    )
    (net (code "53") (name "Net-(U4-XI{slash}CLKN)") (class "Default")
      (node (ref "C55") (pin "1") (pinfunction "1_1") (pintype "passive"))
      (node (ref "R68") (pin "1") (pinfunction "1_1") (pintype "passive"))
      (node (ref "U4") (pin "30") (pinfunction "XI/CLKN_30") (pintype "passive"))
      (node (ref "Y2") (pin "1") (pinfunction "1_1") (pintype "passive"))
    )
    (net (code "54") (name "Net-(U4-XO)") (class "Default")
      (node (ref "R68") (pin "2") (pinfunction "2_2") (pintype "passive"))
      (node (ref "R69") (pin "2") (pinfunction "2_2") (pintype "passive"))
      (node (ref "U4") (pin "31") (pinfunction "XO_31") (pintype "passive"))
    )
    (net (code "55") (name "Net-(Y2-4)") (class "Default")
      (node (ref "C54") (pin "1") (pinfunction "1_1") (pintype "passive"))
      (node (ref "R69") (pin "1") (pinfunction "1_1") (pintype "passive"))
      (node (ref "Y2") (pin "3") (pinfunction "4_3") (pintype "passive"))
    )
    (net (code "56") (name "unconnected-(U2-PA1{slash}UART2_RTS{slash}AIN1-Pad11)") (class "Default")
      (node (ref "U2") (pin "11") (pinfunction "PA1/UART2_RTS/AIN1_11") (pintype "passive"))
    )
    (net (code "57") (name "unconnected-(U2-PA4{slash}SPI1_NSS{slash}AIN4-Pad14)") (class "Default")
      (node (ref "U2") (pin "14") (pinfunction "PA4/SPI1_NSS/AIN4_14") (pintype "passive"))
    )
    (net (code "58") (name "unconnected-(U2-PA5{slash}SPI1_SCK{slash}AIN5-Pad15)") (class "Default")
      (node (ref "U2") (pin "15") (pinfunction "PA5/SPI1_SCK/AIN5_15") (pintype "passive"))
    )
    (net (code "59") (name "unconnected-(U2-PA8{slash}TIM1_CH1-Pad29)") (class "Default")
      (node (ref "U2") (pin "29") (pinfunction "PA8/TIM1_CH1_29") (pintype "passive"))
    )
    (net (code "60") (name "unconnected-(U2-PA12-Pad33)") (class "Default")
      (node (ref "U2") (pin "33") (pinfunction "PA12_33") (pintype "passive"))
    )
    (net (code "61") (name "unconnected-(U2-PB1-Pad19)") (class "Default")
      (node (ref "U2") (pin "19") (pinfunction "PB1_19") (pintype "passive"))
    )
    (net (code "62") (name "unconnected-(U2-PB8{slash}TIM16_CH1-Pad45)") (class "Default")
      (node (ref "U2") (pin "45") (pinfunction "PB8/TIM16_CH1_45") (pintype "passive"))
    )
    (net (code "63") (name "unconnected-(U2-PB9{slash}IR_OUT{slash}TIM17_CH1-Pad46)") (class "Default")
      (node (ref "U2") (pin "46") (pinfunction "PB9/IR_OUT/TIM17_CH1_46") (pintype "passive"))
    )
    (net (code "64") (name "unconnected-(U2-PB10-Pad21)") (class "Default")
      (node (ref "U2") (pin "21") (pinfunction "PB10_21") (pintype "passive"))
    )
    (net (code "65") (name "unconnected-(U2-PB11-Pad22)") (class "Default")
      (node (ref "U2") (pin "22") (pinfunction "PB11_22") (pintype "passive"))
    )
    (net (code "66") (name "unconnected-(U2-PB12{slash}SPI2_NSS-Pad25)") (class "Default")
      (node (ref "U2") (pin "25") (pinfunction "PB12/SPI2_NSS_25") (pintype "passive"))
    )
    (net (code "67") (name "unconnected-(U2-PB13{slash}SPI2_SCK-Pad26)") (class "Default")
      (node (ref "U2") (pin "26") (pinfunction "PB13/SPI2_SCK_26") (pintype "passive"))
    )
    (net (code "68") (name "unconnected-(U2-PB14{slash}SPI2_MISO{slash}TIM15_CH1-Pad27)") (class "Default")
      (node (ref "U2") (pin "27") (pinfunction "PB14/SPI2_MISO/TIM15_CH1_27") (pintype "passive"))
    )
    (net (code "69") (name "unconnected-(U2-PB15{slash}SPI2_MOSI{slash}TIM1_CH3N{slash}TIM15_CH2-Pad28)") (class "Default")
      (node (ref "U2") (pin "28") (pinfunction "PB15/SPI2_MOSI/TIM1_CH3N/TIM15_CH2_28") (pintype "passive"))
    )
    (net (code "70") (name "unconnected-(U2-PC14{slash}OSC32_IN-Pad3)") (class "Default")
      (node (ref "U2") (pin "3") (pinfunction "PC14/OSC32_IN_3") (pintype "passive"))
    )
    (net (code "71") (name "unconnected-(U2-PC15{slash}OSC32_OUT-Pad4)") (class "Default")
      (node (ref "U2") (pin "4") (pinfunction "PC15/OSC32_OUT_4") (pintype "passive"))
    )
    (net (code "72") (name "unconnected-(U4-DNC-Pad7)") (class "Default")
      (node (ref "U4") (pin "7") (pinfunction "DNC_7") (pintype "passive+no_connect"))
    )
    (net (code "73") (name "unconnected-(U4-DUPLED-Pad26)") (class "Default")
      (node (ref "U4") (pin "26") (pinfunction "DUPLED_26") (pintype "passive+no_connect"))
    )
    (net (code "74") (name "unconnected-(U4-NC-Pad12)") (class "Default")
      (node (ref "U4") (pin "12") (pinfunction "NC_12") (pintype "passive+no_connect"))
    )
    (net (code "75") (name "unconnected-(U4-NC-Pad13)") (class "Default")
      (node (ref "U4") (pin "13") (pinfunction "NC_13") (pintype "passive+no_connect"))
    )
    (net (code "76") (name "unconnected-(U4-NC-Pad46)") (class "Default")
      (node (ref "U4") (pin "46") (pinfunction "NC_46") (pintype "passive+no_connect"))
    )
    (net (code "77") (name "unconnected-(U4-NC-Pad47)") (class "Default")
      (node (ref "U4") (pin "47") (pinfunction "NC_47") (pintype "passive+no_connect"))
    )
    (net (code "78") (name "unconnected-(U4-SPDLED-Pad24)") (class "Default")
      (node (ref "U4") (pin "24") (pinfunction "SPDLED_24") (pintype "passive+no_connect"))
    )
    (net (code "79") (name "unconnected-(U4-VBG-Pad18)") (class "Default")
      (node (ref "U4") (pin "18") (pinfunction "VBG_18") (pintype "passive+no_connect"))
    )
  )
)
